# Voltage_Measurment.net
KiCad netlist of a schematic drawn in Altium Designer
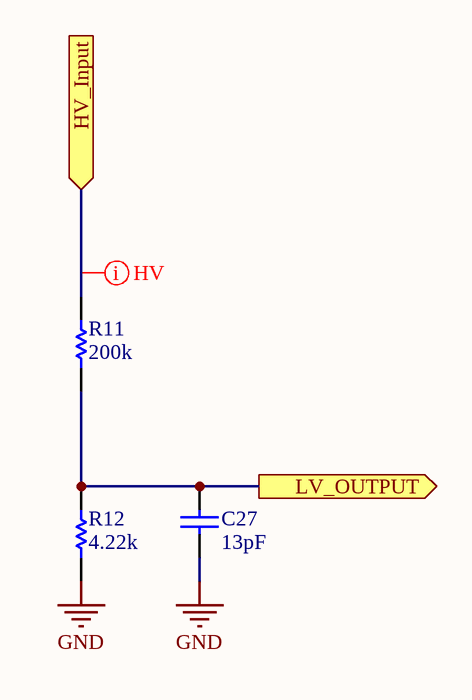
[diagram p0: Voltage_Measurment.SchDoc]

(export (version "E")
  (design (tool "Eeschema 10.0.6"))
  (components
    (comp (ref "C27")
      (value "13pF")
      (footprint "0603_CAPACITOR")
      (fields (field (name "TOLERANCE") "5%") (field (name "Comment") "Capacitor 13pF 0603 5% 50V"))
      (libsource (lib "University of Minnesota - Solar Vehicle Project") (part "Cap"))
    )
    (comp (ref "R11")
      (value "200k")
      (footprint "1206_RESISTOR")
      (description "Resistor 200K 1206 1% 1/4W")
      (fields (field (name "TOLERANCE") "1%") (field (name "POWER") "250mW"))
      (libsource (lib "University of Minnesota - Solar Vehicle Project") (part "RES-2"))
    )
    (comp (ref "R12")
      (value "4.22k")
      (footprint "0603_RESISTOR")
      (fields
        (field (name "TOLERANCE") "1%")
        (field (name "POWER") "100mW")
        (field (name "Comment") "Resistor 4.22k 0603 0.1W 1%")
      )
      (libsource (lib "University of Minnesota - Solar Vehicle Project") (part "RES-2"))
    )
  )
  (nets
    (net (code "1") (name "/HV_Input") (class "Default")
      (node (ref "R11") (pin "2") (pinfunction "2_2") (pintype "passive"))
    )
    (net (code "2") (name "/LV_OUTPUT") (class "Default")
      (node (ref "C27") (pin "2") (pinfunction "2_2") (pintype "passive"))
      (node (ref "R11") (pin "1") (pinfunction "1_1") (pintype "passive"))
      (node (ref "R12") (pin "2") (pinfunction "2_2") (pintype "passive"))
    )
    (net (code "3") (name "GND") (class "Default")
      (node (ref "C27") (pin "1") (pinfunction "1_1") (pintype "passive"))
      (node (ref "R12") (pin "1") (pinfunction "1_1") (pintype "passive"))
    )
  )
)
